# bristol_longshot.net
KiCad netlist of a schematic drawn in EAGLE
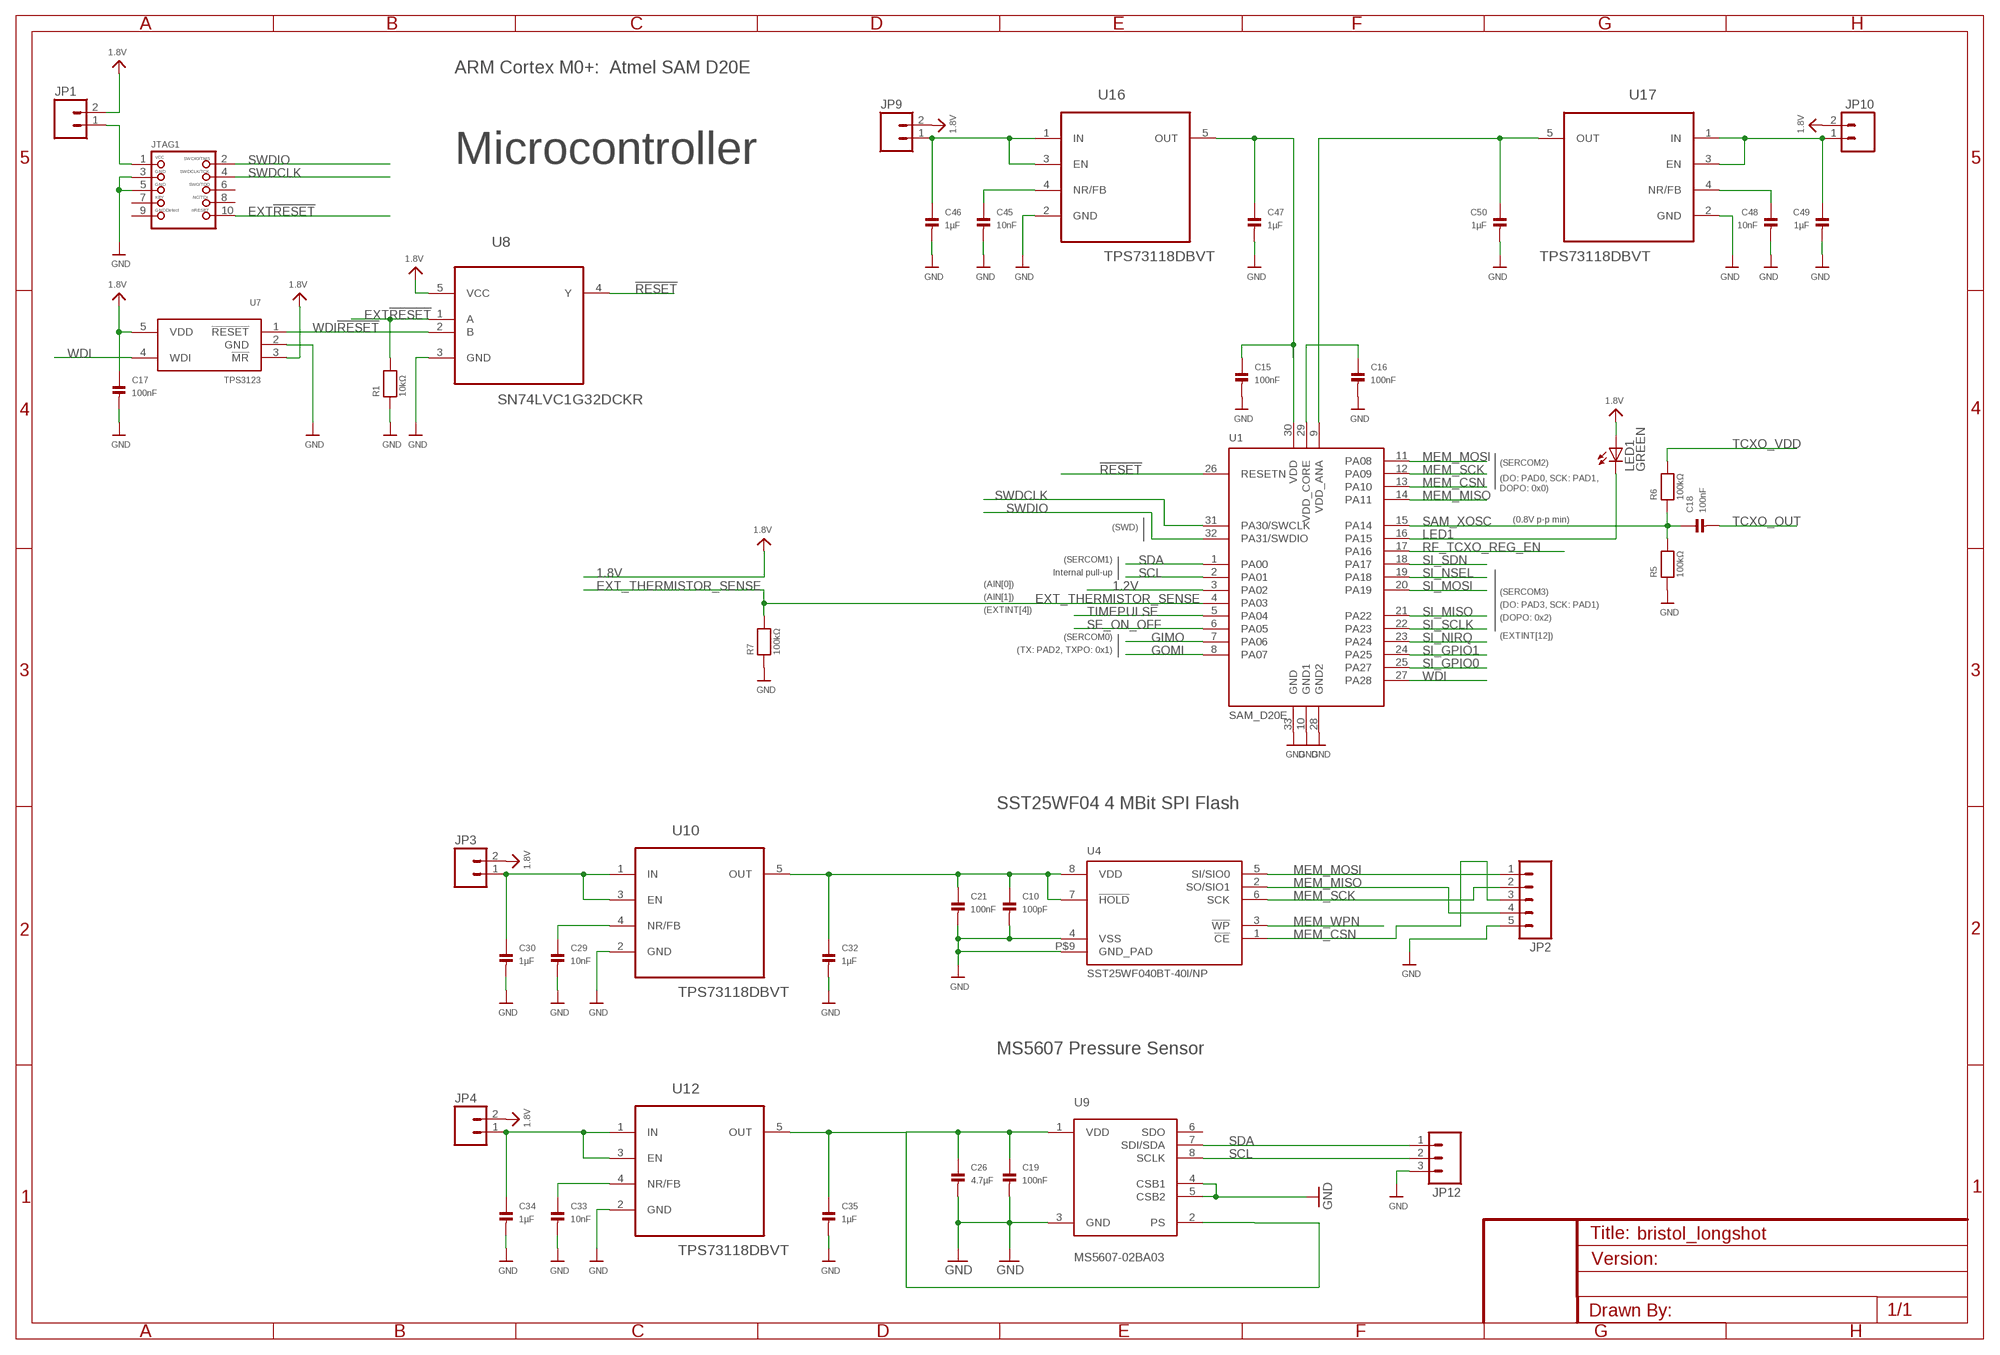
[diagram p0: schematic, sheet 1, part 1 of 2]
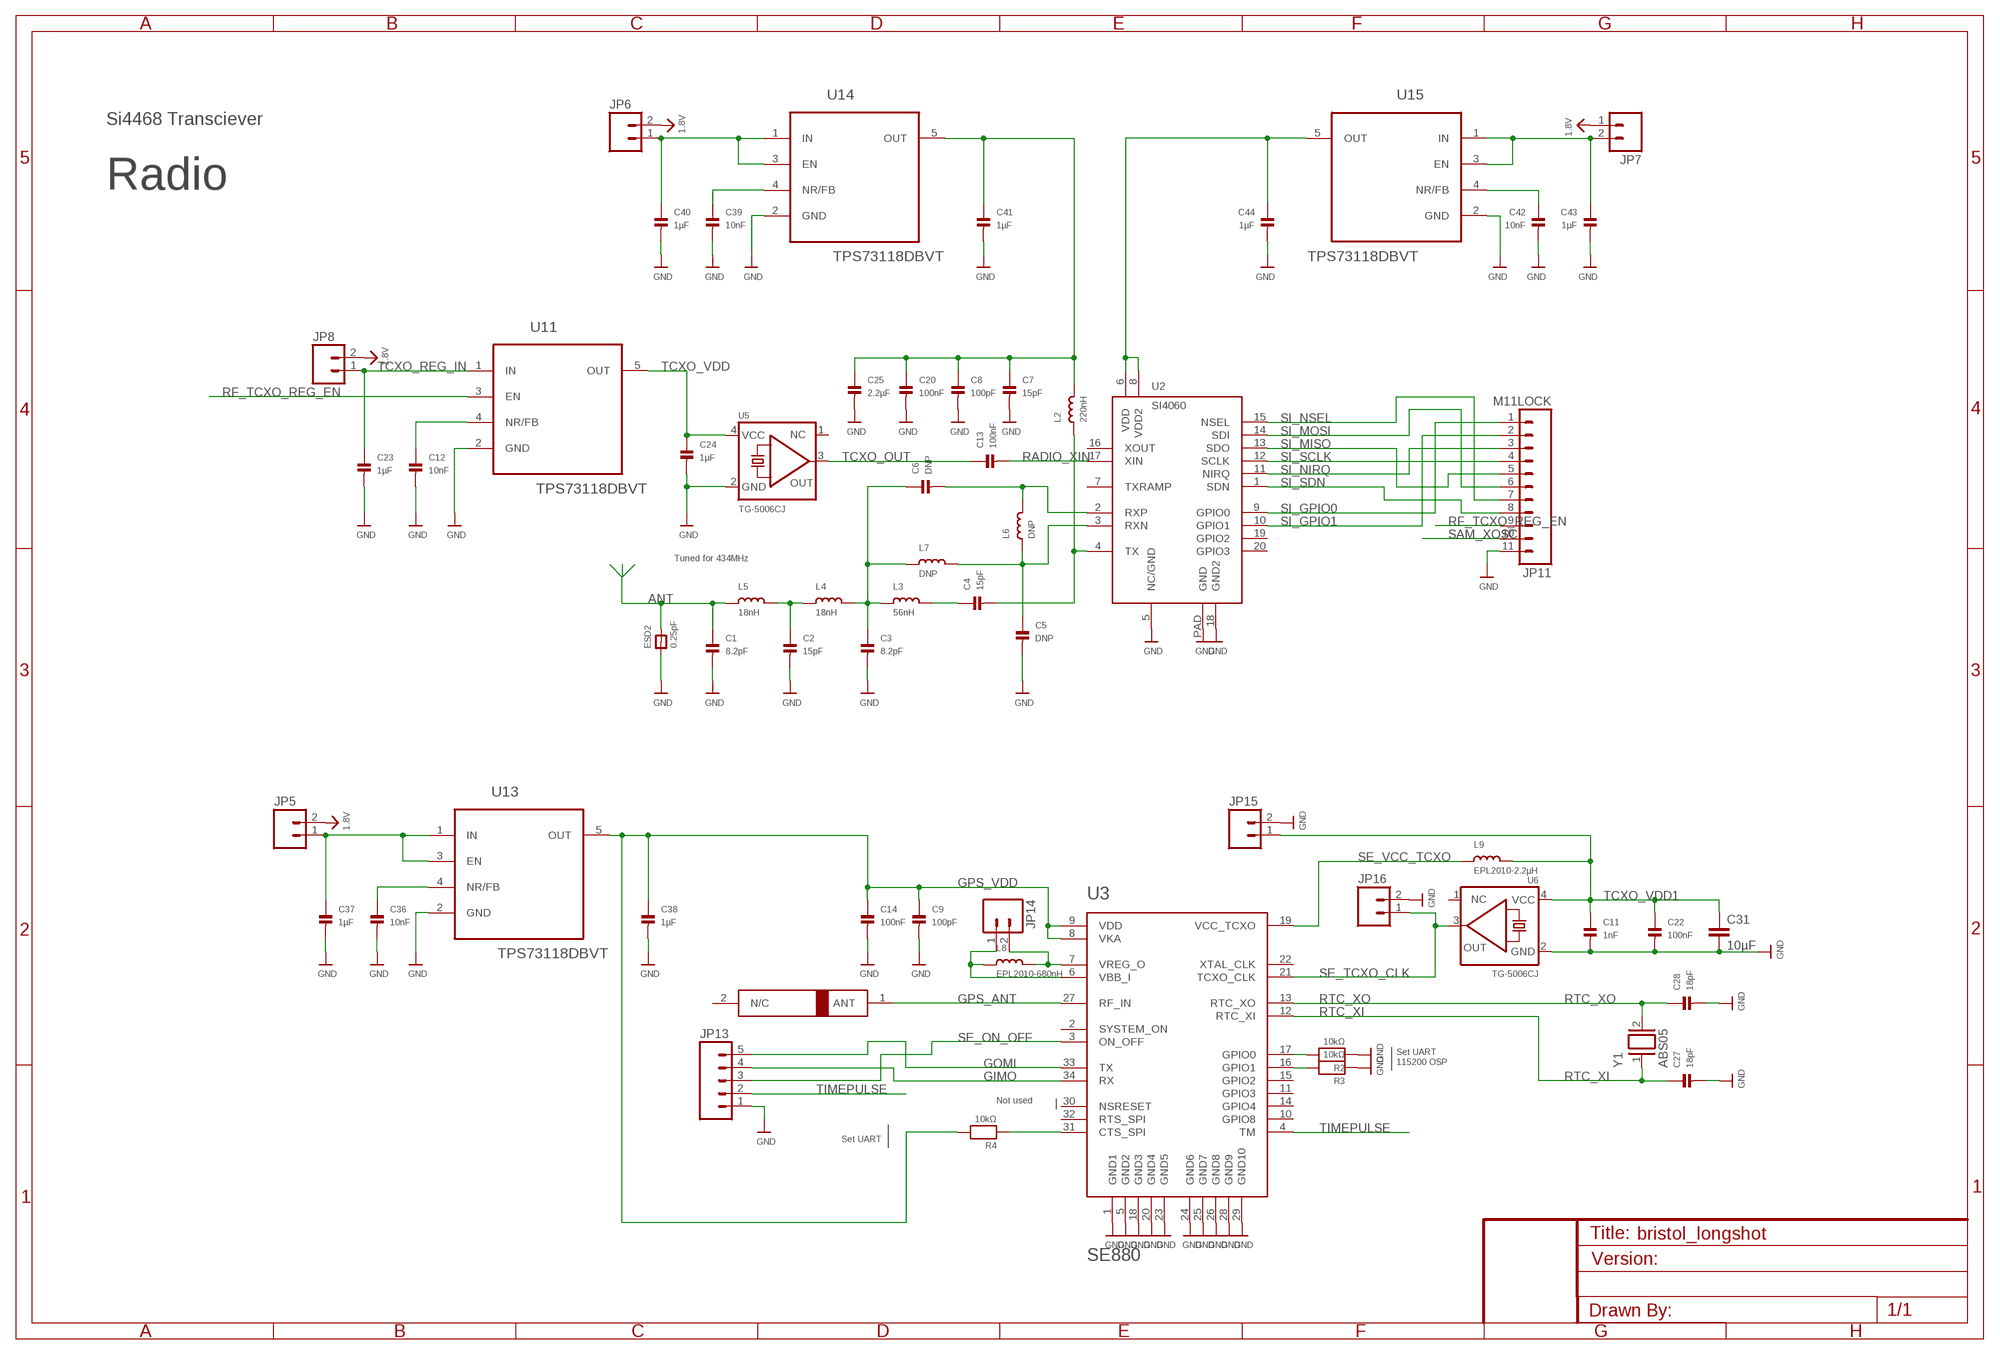
[diagram p1: schematic, sheet 1, part 2 of 2]

(export (version "E")
  (design (tool "Eeschema 10.0.6"))
  (components
    (comp (ref "A1")
      (value "1575AT43A40")
      (footprint "eagle-import:1575AT43A40")
      (libsource (lib "eagle-import") (part "1575AT43A40"))
    )
    (comp (ref "C1")
      (value "8.2pF")
      (footprint "eagle-import:_0402@2")
      (libsource (lib "eagle-import") (part "CAP_CERAMIC_0402"))
    )
    (comp (ref "C2")
      (value "15pF")
      (footprint "eagle-import:_0402@2")
      (libsource (lib "eagle-import") (part "CAP_CERAMIC_0402"))
    )
    (comp (ref "C3")
      (value "8.2pF")
      (footprint "eagle-import:_0402@2")
      (libsource (lib "eagle-import") (part "CAP_CERAMIC_0402"))
    )
    (comp (ref "C4")
      (value "15pF")
      (footprint "eagle-import:_0402@2")
      (libsource (lib "eagle-import") (part "CAP_CERAMIC_0402"))
    )
    (comp (ref "C5")
      (value "DNP")
      (footprint "eagle-import:_0402@2")
      (libsource (lib "eagle-import") (part "CAP_CERAMIC_0402"))
    )
    (comp (ref "C6")
      (value "DNP")
      (footprint "eagle-import:_0402@2")
      (libsource (lib "eagle-import") (part "CAP_CERAMIC_0402"))
    )
    (comp (ref "C7")
      (value "15pF")
      (footprint "eagle-import:_0402@2")
      (libsource (lib "eagle-import") (part "CAP_CERAMIC_0402"))
    )
    (comp (ref "C8")
      (value "100pF")
      (footprint "eagle-import:_0402@2")
      (libsource (lib "eagle-import") (part "CAP_CERAMIC_0402"))
    )
    (comp (ref "C9")
      (value "100pF")
      (footprint "eagle-import:_0402@2")
      (libsource (lib "eagle-import") (part "CAP_CERAMIC_0402"))
    )
    (comp (ref "C10")
      (value "100pF")
      (footprint "eagle-import:_0402@2")
      (libsource (lib "eagle-import") (part "CAP_CERAMIC_0402"))
    )
    (comp (ref "C11")
      (value "1nF")
      (footprint "eagle-import:_0402@2")
      (libsource (lib "eagle-import") (part "CAP_CERAMIC_0402"))
    )
    (comp (ref "C12")
      (value "10nF")
      (footprint "eagle-import:_0402@2")
      (libsource (lib "eagle-import") (part "CAP_CERAMIC_0402"))
    )
    (comp (ref "C13")
      (value "100nF")
      (footprint "eagle-import:_0402@2")
      (libsource (lib "eagle-import") (part "CAP_CERAMIC_0402"))
    )
    (comp (ref "C14")
      (value "100nF")
      (footprint "eagle-import:_0402@2")
      (libsource (lib "eagle-import") (part "CAP_CERAMIC_0402"))
    )
    (comp (ref "C15")
      (value "100nF")
      (footprint "eagle-import:_0402@2")
      (libsource (lib "eagle-import") (part "CAP_CERAMIC_0402"))
    )
    (comp (ref "C16")
      (value "100nF")
      (footprint "eagle-import:_0402@2")
      (libsource (lib "eagle-import") (part "CAP_CERAMIC_0402"))
    )
    (comp (ref "C17")
      (value "100nF")
      (footprint "eagle-import:_0402@2")
      (libsource (lib "eagle-import") (part "CAP_CERAMIC_0402"))
    )
    (comp (ref "C18")
      (value "100nF")
      (footprint "eagle-import:_0402@2")
      (libsource (lib "eagle-import") (part "CAP_CERAMIC_0402"))
    )
    (comp (ref "C19")
      (value "100nF")
      (footprint "eagle-import:_0402@2")
      (libsource (lib "eagle-import") (part "CAP_CERAMIC_0402"))
    )
    (comp (ref "C20")
      (value "100nF")
      (footprint "eagle-import:_0402@2")
      (libsource (lib "eagle-import") (part "CAP_CERAMIC_0402"))
    )
    (comp (ref "C21")
      (value "100nF")
      (footprint "eagle-import:_0402@2")
      (libsource (lib "eagle-import") (part "CAP_CERAMIC_0402"))
    )
    (comp (ref "C22")
      (value "100nF")
      (footprint "eagle-import:_0402@2")
      (libsource (lib "eagle-import") (part "CAP_CERAMIC_0402"))
    )
    (comp (ref "C23")
      (value "1µF")
      (footprint "eagle-import:_0402@2")
      (libsource (lib "eagle-import") (part "CAP_CERAMIC_0402"))
    )
    (comp (ref "C24")
      (value "1µF")
      (footprint "eagle-import:_0402@2")
      (libsource (lib "eagle-import") (part "CAP_CERAMIC_0402"))
    )
    (comp (ref "C25")
      (value "2.2µF")
      (footprint "eagle-import:_0402@2")
      (libsource (lib "eagle-import") (part "CAP_CERAMIC_0402"))
    )
    (comp (ref "C26")
      (value "4.7µF")
      (footprint "eagle-import:_0402@2")
      (libsource (lib "eagle-import") (part "CAP_CERAMIC_0402"))
    )
    (comp (ref "C27")
      (value "18pF")
      (footprint "eagle-import:_0402@2")
      (libsource (lib "eagle-import") (part "CAP_CERAMIC_0402"))
    )
    (comp (ref "C28")
      (value "18pF")
      (footprint "eagle-import:_0402@2")
      (libsource (lib "eagle-import") (part "CAP_CERAMIC_0402"))
    )
    (comp (ref "C29")
      (value "10nF")
      (footprint "eagle-import:_0402@2")
      (libsource (lib "eagle-import") (part "CAP_CERAMIC_0402"))
    )
    (comp (ref "C30")
      (value "1µF")
      (footprint "eagle-import:_0402@2")
      (libsource (lib "eagle-import") (part "CAP_CERAMIC_0402"))
    )
    (comp (ref "C31")
      (value "10µF")
      (footprint "eagle-import:C0603K")
      (libsource (lib "eagle-import") (part "C-EUC0603K"))
    )
    (comp (ref "C32")
      (value "1µF")
      (footprint "eagle-import:_0402@2")
      (libsource (lib "eagle-import") (part "CAP_CERAMIC_0402"))
    )
    (comp (ref "C33")
      (value "10nF")
      (footprint "eagle-import:_0402@2")
      (libsource (lib "eagle-import") (part "CAP_CERAMIC_0402"))
    )
    (comp (ref "C34")
      (value "1µF")
      (footprint "eagle-import:_0402@2")
      (libsource (lib "eagle-import") (part "CAP_CERAMIC_0402"))
    )
    (comp (ref "C35")
      (value "1µF")
      (footprint "eagle-import:_0402@2")
      (libsource (lib "eagle-import") (part "CAP_CERAMIC_0402"))
    )
    (comp (ref "C36")
      (value "10nF")
      (footprint "eagle-import:_0402@2")
      (libsource (lib "eagle-import") (part "CAP_CERAMIC_0402"))
    )
    (comp (ref "C37")
      (value "1µF")
      (footprint "eagle-import:_0402@2")
      (libsource (lib "eagle-import") (part "CAP_CERAMIC_0402"))
    )
    (comp (ref "C38")
      (value "1µF")
      (footprint "eagle-import:_0402@2")
      (libsource (lib "eagle-import") (part "CAP_CERAMIC_0402"))
    )
    (comp (ref "C39")
      (value "10nF")
      (footprint "eagle-import:_0402@2")
      (libsource (lib "eagle-import") (part "CAP_CERAMIC_0402"))
    )
    (comp (ref "C40")
      (value "1µF")
      (footprint "eagle-import:_0402@2")
      (libsource (lib "eagle-import") (part "CAP_CERAMIC_0402"))
    )
    (comp (ref "C41")
      (value "1µF")
      (footprint "eagle-import:_0402@2")
      (libsource (lib "eagle-import") (part "CAP_CERAMIC_0402"))
    )
    (comp (ref "C42")
      (value "10nF")
      (footprint "eagle-import:_0402@2")
      (libsource (lib "eagle-import") (part "CAP_CERAMIC_0402"))
    )
    (comp (ref "C43")
      (value "1µF")
      (footprint "eagle-import:_0402@2")
      (libsource (lib "eagle-import") (part "CAP_CERAMIC_0402"))
    )
    (comp (ref "C44")
      (value "1µF")
      (footprint "eagle-import:_0402@2")
      (libsource (lib "eagle-import") (part "CAP_CERAMIC_0402"))
    )
    (comp (ref "C45")
      (value "10nF")
      (footprint "eagle-import:_0402@2")
      (libsource (lib "eagle-import") (part "CAP_CERAMIC_0402"))
    )
    (comp (ref "C46")
      (value "1µF")
      (footprint "eagle-import:_0402@2")
      (libsource (lib "eagle-import") (part "CAP_CERAMIC_0402"))
    )
    (comp (ref "C47")
      (value "1µF")
      (footprint "eagle-import:_0402@2")
      (libsource (lib "eagle-import") (part "CAP_CERAMIC_0402"))
    )
    (comp (ref "C48")
      (value "10nF")
      (footprint "eagle-import:_0402@2")
      (libsource (lib "eagle-import") (part "CAP_CERAMIC_0402"))
    )
    (comp (ref "C49")
      (value "1µF")
      (footprint "eagle-import:_0402@2")
      (libsource (lib "eagle-import") (part "CAP_CERAMIC_0402"))
    )
    (comp (ref "C50")
      (value "1µF")
      (footprint "eagle-import:_0402@2")
      (libsource (lib "eagle-import") (part "CAP_CERAMIC_0402"))
    )
    (comp (ref "ESD2")
      (value "0.25pF")
      (footprint "eagle-import:_0603MP")
      (libsource (lib "eagle-import") (part "FERRITE_0603MP"))
    )
    (comp (ref "JP1")
      (value "M02LOCK")
      (footprint "eagle-import:1X02_LOCK")
      (libsource (lib "eagle-import") (part "M02LOCK"))
    )
    (comp (ref "JP2")
      (value "M05LOCK")
      (footprint "eagle-import:1X05_LOCK")
      (libsource (lib "eagle-import") (part "M05LOCK"))
    )
    (comp (ref "JP3")
      (value "M02LOCK")
      (footprint "eagle-import:1X02_LOCK")
      (libsource (lib "eagle-import") (part "M02LOCK"))
    )
    (comp (ref "JP4")
      (value "M02LOCK")
      (footprint "eagle-import:1X02_LOCK")
      (libsource (lib "eagle-import") (part "M02LOCK"))
    )
    (comp (ref "JP5")
      (value "M02LOCK")
      (footprint "eagle-import:1X02_LOCK")
      (libsource (lib "eagle-import") (part "M02LOCK"))
    )
    (comp (ref "JP6")
      (value "M02LOCK")
      (footprint "eagle-import:1X02_LOCK")
      (libsource (lib "eagle-import") (part "M02LOCK"))
    )
    (comp (ref "JP7")
      (value "M02LOCK")
      (footprint "eagle-import:1X02_LOCK")
      (libsource (lib "eagle-import") (part "M02LOCK"))
    )
    (comp (ref "JP8")
      (value "M02LOCK")
      (footprint "eagle-import:1X02_LOCK")
      (libsource (lib "eagle-import") (part "M02LOCK"))
    )
    (comp (ref "JP9")
      (value "M02LOCK")
      (footprint "eagle-import:1X02_LOCK")
      (libsource (lib "eagle-import") (part "M02LOCK"))
    )
    (comp (ref "JP10")
      (value "M02LOCK")
      (footprint "eagle-import:1X02_LOCK")
      (libsource (lib "eagle-import") (part "M02LOCK"))
    )
    (comp (ref "JP11")
      (value "M11LOCK")
      (footprint "eagle-import:1X11_LOCK")
      (libsource (lib "eagle-import") (part "M11LOCK"))
    )
    (comp (ref "JP12")
      (value "M03LOCK")
      (footprint "eagle-import:1X03_LOCK")
      (libsource (lib "eagle-import") (part "M03LOCK"))
    )
    (comp (ref "JP13")
      (value "M05LOCK")
      (footprint "eagle-import:1X05_LOCK")
      (libsource (lib "eagle-import") (part "M05LOCK"))
    )
    (comp (ref "JP14")
      (value "M02LOCK")
      (footprint "eagle-import:1X02_LOCK")
      (libsource (lib "eagle-import") (part "M02LOCK"))
    )
    (comp (ref "JP15")
      (value "M02LOCK")
      (footprint "eagle-import:1X02_LOCK")
      (libsource (lib "eagle-import") (part "M02LOCK"))
    )
    (comp (ref "JP16")
      (value "M02LOCK")
      (footprint "eagle-import:1X02_LOCK")
      (libsource (lib "eagle-import") (part "M02LOCK"))
    )
    (comp (ref "JTAG1")
      (value "JTAG-CORTEXM3SMT")
      (footprint "eagle-import:2X05_1.27MM_SMT")
      (libsource (lib "eagle-import") (part "JTAG-CORTEXM3SMT"))
    )
    (comp (ref "L2")
      (value "220nH")
      (footprint "eagle-import:_0402@1")
      (libsource (lib "eagle-import") (part "INDUCTOR_0402"))
    )
    (comp (ref "L3")
      (value "56nH")
      (footprint "eagle-import:_0402@1")
      (libsource (lib "eagle-import") (part "INDUCTOR_0402"))
    )
    (comp (ref "L4")
      (value "18nH")
      (footprint "eagle-import:_0402@1")
      (libsource (lib "eagle-import") (part "INDUCTOR_0402"))
    )
    (comp (ref "L5")
      (value "18nH")
      (footprint "eagle-import:_0402@1")
      (libsource (lib "eagle-import") (part "INDUCTOR_0402"))
    )
    (comp (ref "L6")
      (value "DNP")
      (footprint "eagle-import:_0402@1")
      (libsource (lib "eagle-import") (part "INDUCTOR_0402"))
    )
    (comp (ref "L7")
      (value "DNP")
      (footprint "eagle-import:_0402@1")
      (libsource (lib "eagle-import") (part "INDUCTOR_0402"))
    )
    (comp (ref "L8")
      (value "EPL2010-680nH")
      (footprint "eagle-import:EPL2010")
      (libsource (lib "eagle-import") (part "EPL2010"))
    )
    (comp (ref "L9")
      (value "EPL2010-2.2µH")
      (footprint "eagle-import:EPL2010")
      (libsource (lib "eagle-import") (part "EPL2010"))
    )
    (comp (ref "LED1")
      (value "GREEN")
      (footprint "eagle-import:CHIPLED_0603")
      (libsource (lib "eagle-import") (part "LEDCHIPLED_0603"))
    )
    (comp (ref "R1")
      (value "10kΩ")
      (footprint "eagle-import:_0402")
      (libsource (lib "eagle-import") (part "RESISTOR_0402"))
    )
    (comp (ref "R2")
      (value "10kΩ")
      (footprint "eagle-import:_0402")
      (libsource (lib "eagle-import") (part "RESISTOR_0402"))
    )
    (comp (ref "R3")
      (value "10kΩ")
      (footprint "eagle-import:_0402")
      (libsource (lib "eagle-import") (part "RESISTOR_0402"))
    )
    (comp (ref "R4")
      (value "10kΩ")
      (footprint "eagle-import:_0402")
      (libsource (lib "eagle-import") (part "RESISTOR_0402"))
    )
    (comp (ref "R5")
      (value "100kΩ")
      (footprint "eagle-import:_0402")
      (libsource (lib "eagle-import") (part "RESISTOR_0402"))
    )
    (comp (ref "R6")
      (value "100kΩ")
      (footprint "eagle-import:_0402")
      (libsource (lib "eagle-import") (part "RESISTOR_0402"))
    )
    (comp (ref "R7")
      (value "100kΩ")
      (footprint "eagle-import:_0402")
      (libsource (lib "eagle-import") (part "RESISTOR_0402"))
    )
    (comp (ref "U1")
      (value "SAM_D20E")
      (footprint "eagle-import:QFN32_5MM")
      (libsource (lib "eagle-import") (part "SAM_D20E"))
    )
    (comp (ref "U2")
      (value "SI4060")
      (footprint "eagle-import:QFN20")
      (libsource (lib "eagle-import") (part "SI4060"))
    )
    (comp (ref "U3")
      (value "SE880")
      (footprint "eagle-import:SE880")
      (libsource (lib "eagle-import") (part "SE880"))
    )
    (comp (ref "U4")
      (value "SST25WF040BT-40I/NP")
      (footprint "eagle-import:USON-8")
      (libsource (lib "eagle-import") (part "SST25WF040BT-40I/NP"))
    )
    (comp (ref "U5")
      (value "TG-5006CJ")
      (footprint "eagle-import:TC-5006CJ")
      (libsource (lib "eagle-import") (part "TG-5006CJ"))
    )
    (comp (ref "U6")
      (value "TG-5006CJ")
      (footprint "eagle-import:TC-5006CJ")
      (libsource (lib "eagle-import") (part "TG-5006CJ"))
    )
    (comp (ref "U7")
      (value "TPS3123")
      (footprint "eagle-import:SOT23-5")
      (libsource (lib "eagle-import") (part "TPS3123"))
    )
    (comp (ref "U8")
      (value "SN74LVC1G32DCKR")
      (footprint "eagle-import:SOT65P210X110-5N")
      (libsource (lib "eagle-import") (part "SN74LVC1G32DCKR"))
    )
    (comp (ref "U9")
      (value "MS5607-02BA03")
      (footprint "eagle-import:MS5607-02BA03")
      (libsource (lib "eagle-import") (part "MS5607-02BA03"))
    )
    (comp (ref "U10")
      (value "TPS73118DBVT")
      (footprint "eagle-import:SOT95P280X145-5N")
      (libsource (lib "eagle-import") (part "TPS73118DBVT"))
    )
    (comp (ref "U11")
      (value "TPS73118DBVT")
      (footprint "eagle-import:SOT95P280X145-5N")
      (libsource (lib "eagle-import") (part "TPS73118DBVT"))
    )
    (comp (ref "U12")
      (value "TPS73118DBVT")
      (footprint "eagle-import:SOT95P280X145-5N")
      (libsource (lib "eagle-import") (part "TPS73118DBVT"))
    )
    (comp (ref "U13")
      (value "TPS73118DBVT")
      (footprint "eagle-import:SOT95P280X145-5N")
      (libsource (lib "eagle-import") (part "TPS73118DBVT"))
    )
    (comp (ref "U14")
      (value "TPS73118DBVT")
      (footprint "eagle-import:SOT95P280X145-5N")
      (libsource (lib "eagle-import") (part "TPS73118DBVT"))
    )
    (comp (ref "U15")
      (value "TPS73118DBVT")
      (footprint "eagle-import:SOT95P280X145-5N")
      (libsource (lib "eagle-import") (part "TPS73118DBVT"))
    )
    (comp (ref "U16")
      (value "TPS73118DBVT")
      (footprint "eagle-import:SOT95P280X145-5N")
      (libsource (lib "eagle-import") (part "TPS73118DBVT"))
    )
    (comp (ref "U17")
      (value "TPS73118DBVT")
      (footprint "eagle-import:SOT95P280X145-5N")
      (libsource (lib "eagle-import") (part "TPS73118DBVT"))
    )
    (comp (ref "Y1")
      (value "ABS05")
      (footprint "eagle-import:ABS05")
      (libsource (lib "eagle-import") (part "ABS05"))
    )
  )
  (nets
    (net (code "1") (name "/1.2V") (class "Default")
      (node (ref "U1") (pin "3") (pinfunction "PA02_3") (pintype "bidirectional"))
    )
    (net (code "2") (name "/ANT") (class "Default")
      (node (ref "C1") (pin "1") (pinfunction "P$1_1") (pintype "passive"))
      (node (ref "ESD2") (pin "2") (pinfunction "P$2_2") (pintype "passive"))
      (node (ref "L5") (pin "1") (pinfunction "1_1") (pintype "passive"))
    )
    (net (code "3") (name "/EXT_THERMISTOR_SENSE") (class "Default")
      (node (ref "R7") (pin "2") (pinfunction "2_2") (pintype "passive"))
      (node (ref "U1") (pin "4") (pinfunction "PA03_4") (pintype "bidirectional"))
    )
    (net (code "4") (name "/EXT~{RESET}") (class "Default")
      (node (ref "JTAG1") (pin "10") (pinfunction "10_10") (pintype "passive"))
      (node (ref "R1") (pin "2") (pinfunction "2_2") (pintype "passive"))
      (node (ref "U8") (pin "1") (pinfunction "A_1") (pintype "input"))
    )
    (net (code "5") (name "/GIMO") (class "Default")
      (node (ref "JP13") (pin "4") (pinfunction "4_4") (pintype "passive"))
      (node (ref "U1") (pin "7") (pinfunction "PA06_7") (pintype "bidirectional"))
      (node (ref "U3") (pin "34") (pinfunction "RX_34") (pintype "bidirectional"))
    )
    (net (code "6") (name "/GOMI") (class "Default")
      (node (ref "JP13") (pin "5") (pinfunction "5_5") (pintype "passive"))
      (node (ref "U1") (pin "8") (pinfunction "PA07_8") (pintype "bidirectional"))
      (node (ref "U3") (pin "33") (pinfunction "TX_33") (pintype "bidirectional"))
    )
    (net (code "7") (name "/GPS_ANT") (class "Default")
      (node (ref "A1") (pin "1") (pinfunction "ANT_1") (pintype "bidirectional"))
      (node (ref "U3") (pin "27") (pinfunction "RF_IN_27") (pintype "bidirectional"))
    )
    (net (code "8") (name "/GPS_VDD") (class "Default")
      (node (ref "C14") (pin "1") (pinfunction "P$1_1") (pintype "passive"))
      (node (ref "C38") (pin "1") (pinfunction "P$1_1") (pintype "passive"))
      (node (ref "C9") (pin "1") (pinfunction "P$1_1") (pintype "passive"))
      (node (ref "R4") (pin "2") (pinfunction "2_2") (pintype "passive"))
      (node (ref "U13") (pin "5") (pinfunction "OUT_5") (pintype "output"))
      (node (ref "U3") (pin "8") (pinfunction "VKA_8") (pintype "bidirectional"))
      (node (ref "U3") (pin "9") (pinfunction "VDD_9") (pintype "bidirectional"))
    )
    (net (code "9") (name "/LED1") (class "Default")
      (node (ref "LED1") (pin "C") (pinfunction "C_C") (pintype "passive"))
      (node (ref "U1") (pin "16") (pinfunction "PA15_16") (pintype "bidirectional"))
    )
    (net (code "10") (name "/MEM_CSN") (class "Default")
      (node (ref "JP2") (pin "3") (pinfunction "3_3") (pintype "passive"))
      (node (ref "U1") (pin "13") (pinfunction "PA10_13") (pintype "bidirectional"))
      (node (ref "U4") (pin "1") (pinfunction "~{CE}_1") (pintype "input"))
    )
    (net (code "11") (name "/MEM_MISO") (class "Default")
      (node (ref "JP2") (pin "4") (pinfunction "4_4") (pintype "passive"))
      (node (ref "U1") (pin "14") (pinfunction "PA11_14") (pintype "bidirectional"))
      (node (ref "U4") (pin "2") (pinfunction "SO/SIO1_2") (pintype "output"))
    )
    (net (code "12") (name "/MEM_MOSI") (class "Default")
      (node (ref "JP2") (pin "1") (pinfunction "1_1") (pintype "passive"))
      (node (ref "U1") (pin "11") (pinfunction "PA08_11") (pintype "bidirectional"))
      (node (ref "U4") (pin "5") (pinfunction "SI/SIO0_5") (pintype "bidirectional"))
    )
    (net (code "13") (name "/MEM_SCK") (class "Default")
      (node (ref "JP2") (pin "2") (pinfunction "2_2") (pintype "passive"))
      (node (ref "U1") (pin "12") (pinfunction "PA09_12") (pintype "bidirectional"))
      (node (ref "U4") (pin "6") (pinfunction "SCK_6") (pintype "input"))
    )
    (net (code "14") (name "/MEM_WPN") (class "Default")
      (node (ref "U4") (pin "3") (pinfunction "~{WP}_3") (pintype "output"))
    )
    (net (code "15") (name "/RADIO_XIN") (class "Default")
      (node (ref "C13") (pin "2") (pinfunction "P$2_2") (pintype "passive"))
      (node (ref "U2") (pin "17") (pinfunction "XIN_17") (pintype "input"))
    )
    (net (code "16") (name "/RF_TCXO_REG_EN") (class "Default")
      (node (ref "JP11") (pin "9") (pinfunction "9_9") (pintype "passive"))
      (node (ref "U1") (pin "17") (pinfunction "PA16_17") (pintype "bidirectional"))
      (node (ref "U11") (pin "3") (pinfunction "EN_3") (pintype "input"))
    )
    (net (code "17") (name "/RTC_XI") (class "Default")
      (node (ref "C27") (pin "1") (pinfunction "P$1_1") (pintype "passive"))
      (node (ref "U3") (pin "12") (pinfunction "RTC_XI_12") (pintype "bidirectional"))
      (node (ref "Y1") (pin "1") (pinfunction "1_1") (pintype "passive"))
    )
    (net (code "18") (name "/RTC_XO") (class "Default")
      (node (ref "C28") (pin "1") (pinfunction "P$1_1") (pintype "passive"))
      (node (ref "U3") (pin "13") (pinfunction "RTC_XO_13") (pintype "bidirectional"))
      (node (ref "Y1") (pin "2") (pinfunction "2_2") (pintype "passive"))
    )
    (net (code "19") (name "/SAM_XOSC") (class "Default")
      (node (ref "C18") (pin "1") (pinfunction "P$1_1") (pintype "passive"))
      (node (ref "JP11") (pin "10") (pinfunction "10_10") (pintype "passive"))
      (node (ref "R5") (pin "2") (pinfunction "2_2") (pintype "passive"))
      (node (ref "R6") (pin "1") (pinfunction "1_1") (pintype "passive"))
      (node (ref "U1") (pin "15") (pinfunction "PA14_15") (pintype "bidirectional"))
    )
    (net (code "20") (name "/SCL") (class "Default")
      (node (ref "JP12") (pin "2") (pinfunction "2_2") (pintype "passive"))
      (node (ref "U1") (pin "2") (pinfunction "PA01_2") (pintype "bidirectional"))
      (node (ref "U9") (pin "8") (pinfunction "SCLK_8") (pintype "bidirectional"))
    )
    (net (code "21") (name "/SDA") (class "Default")
      (node (ref "JP12") (pin "1") (pinfunction "1_1") (pintype "passive"))
      (node (ref "U1") (pin "1") (pinfunction "PA00_1") (pintype "bidirectional"))
      (node (ref "U9") (pin "7") (pinfunction "SDI/SDA_7") (pintype "bidirectional"))
    )
    (net (code "22") (name "/SE_ON_OFF") (class "Default")
      (node (ref "JP13") (pin "3") (pinfunction "3_3") (pintype "passive"))
      (node (ref "U1") (pin "6") (pinfunction "PA05_6") (pintype "bidirectional"))
      (node (ref "U3") (pin "3") (pinfunction "ON_OFF_3") (pintype "bidirectional"))
    )
    (net (code "23") (name "/SE_TCXO_CLK") (class "Default")
      (node (ref "JP16") (pin "1") (pinfunction "1_1") (pintype "passive"))
      (node (ref "U3") (pin "21") (pinfunction "TCXO_CLK_21") (pintype "bidirectional"))
      (node (ref "U6") (pin "3") (pinfunction "OUT_3") (pintype "output"))
    )
    (net (code "24") (name "/SE_VCC_TCXO") (class "Default")
      (node (ref "L9") (pin "1") (pinfunction "1_1") (pintype "passive"))
      (node (ref "U3") (pin "19") (pinfunction "VCC_TCXO_19") (pintype "bidirectional"))
    )
    (net (code "25") (name "/SI_GPIO0") (class "Default")
      (node (ref "JP11") (pin "1") (pinfunction "1_1") (pintype "passive"))
      (node (ref "U1") (pin "25") (pinfunction "PA27_25") (pintype "bidirectional"))
      (node (ref "U2") (pin "9") (pinfunction "GPIO0_9") (pintype "bidirectional"))
    )
    (net (code "26") (name "/SI_GPIO1") (class "Default")
      (node (ref "JP11") (pin "2") (pinfunction "2_2") (pintype "passive"))
      (node (ref "U1") (pin "24") (pinfunction "PA25_24") (pintype "bidirectional"))
      (node (ref "U2") (pin "10") (pinfunction "GPIO1_10") (pintype "bidirectional"))
    )
    (net (code "27") (name "/SI_MISO") (class "Default")
      (node (ref "JP11") (pin "5") (pinfunction "5_5") (pintype "passive"))
      (node (ref "U1") (pin "21") (pinfunction "PA22_21") (pintype "bidirectional"))
      (node (ref "U2") (pin "13") (pinfunction "SDO_13") (pintype "output"))
    )
    (net (code "28") (name "/SI_MOSI") (class "Default")
      (node (ref "JP11") (pin "6") (pinfunction "6_6") (pintype "passive"))
      (node (ref "U1") (pin "20") (pinfunction "PA19_20") (pintype "bidirectional"))
      (node (ref "U2") (pin "14") (pinfunction "SDI_14") (pintype "bidirectional"))
    )
    (net (code "29") (name "/SI_NIRQ") (class "Default")
      (node (ref "JP11") (pin "3") (pinfunction "3_3") (pintype "passive"))
      (node (ref "U1") (pin "23") (pinfunction "PA24_23") (pintype "bidirectional"))
      (node (ref "U2") (pin "11") (pinfunction "NIRQ_11") (pintype "output"))
    )
    (net (code "30") (name "/SI_NSEL") (class "Default")
      (node (ref "JP11") (pin "7") (pinfunction "7_7") (pintype "passive"))
      (node (ref "U1") (pin "19") (pinfunction "PA18_19") (pintype "bidirectional"))
      (node (ref "U2") (pin "15") (pinfunction "NSEL_15") (pintype "input"))
    )
    (net (code "31") (name "/SI_SCLK") (class "Default")
      (node (ref "JP11") (pin "4") (pinfunction "4_4") (pintype "passive"))
      (node (ref "U1") (pin "22") (pinfunction "PA23_22") (pintype "bidirectional"))
      (node (ref "U2") (pin "12") (pinfunction "SCLK_12") (pintype "input"))
    )
    (net (code "32") (name "/SI_SDN") (class "Default")
      (node (ref "JP11") (pin "8") (pinfunction "8_8") (pintype "passive"))
      (node (ref "U1") (pin "18") (pinfunction "PA17_18") (pintype "bidirectional"))
      (node (ref "U2") (pin "1") (pinfunction "SDN_1") (pintype "input"))
    )
    (net (code "33") (name "/SWDCLK") (class "Default")
      (node (ref "JTAG1") (pin "4") (pinfunction "4_4") (pintype "passive"))
      (node (ref "U1") (pin "31") (pinfunction "PA30/SWCLK_31") (pintype "bidirectional"))
    )
    (net (code "34") (name "/SWDIO") (class "Default")
      (node (ref "JTAG1") (pin "2") (pinfunction "2_2") (pintype "passive"))
      (node (ref "U1") (pin "32") (pinfunction "PA31/SWDIO_32") (pintype "bidirectional"))
    )
    (net (code "35") (name "/TCXO_OUT") (class "Default")
      (node (ref "C13") (pin "1") (pinfunction "P$1_1") (pintype "passive"))
      (node (ref "C18") (pin "2") (pinfunction "P$2_2") (pintype "passive"))
      (node (ref "U5") (pin "3") (pinfunction "OUT_3") (pintype "output"))
    )
    (net (code "36") (name "/TCXO_REG_IN") (class "Default")
      (node (ref "C23") (pin "1") (pinfunction "P$1_1") (pintype "passive"))
      (node (ref "JP8") (pin "1") (pinfunction "1_1") (pintype "passive"))
      (node (ref "U11") (pin "1") (pinfunction "IN_1") (pintype "power_in"))
    )
    (net (code "37") (name "/TCXO_VDD") (class "Default")
      (node (ref "C24") (pin "1") (pinfunction "P$1_1") (pintype "passive"))
      (node (ref "R6") (pin "2") (pinfunction "2_2") (pintype "passive"))
      (node (ref "U11") (pin "5") (pinfunction "OUT_5") (pintype "output"))
      (node (ref "U5") (pin "4") (pinfunction "VCC_4") (pintype "power_in"))
    )
    (net (code "38") (name "/TCXO_VDD1") (class "Default")
      (node (ref "C11") (pin "1") (pinfunction "P$1_1") (pintype "passive"))
      (node (ref "C22") (pin "1") (pinfunction "P$1_1") (pintype "passive"))
      (node (ref "C31") (pin "1") (pinfunction "1_1") (pintype "passive"))
      (node (ref "JP15") (pin "1") (pinfunction "1_1") (pintype "passive"))
      (node (ref "L9") (pin "2") (pinfunction "2_2") (pintype "passive"))
      (node (ref "U6") (pin "4") (pinfunction "VCC_4") (pintype "power_in"))
    )
    (net (code "39") (name "/TIMEPULSE") (class "Default")
      (node (ref "JP13") (pin "2") (pinfunction "2_2") (pintype "passive"))
      (node (ref "U1") (pin "5") (pinfunction "PA04_5") (pintype "bidirectional"))
      (node (ref "U3") (pin "4") (pinfunction "TM_4") (pintype "bidirectional"))
    )
    (net (code "40") (name "/WDI") (class "Default")
      (node (ref "U1") (pin "27") (pinfunction "PA28_27") (pintype "bidirectional"))
      (node (ref "U7") (pin "4") (pinfunction "WDI_4") (pintype "bidirectional"))
    )
    (net (code "41") (name "/WDI~{RESET}") (class "Default")
      (node (ref "U7") (pin "1") (pinfunction "~{RESET}_1") (pintype "bidirectional"))
      (node (ref "U8") (pin "2") (pinfunction "B_2") (pintype "input"))
    )
    (net (code "42") (name "/~{RESET}") (class "Default")
      (node (ref "U1") (pin "26") (pinfunction "RESETN_26") (pintype "input"))
      (node (ref "U8") (pin "4") (pinfunction "Y_4") (pintype "output"))
    )
    (net (code "43") (name "1.8V") (class "Default")
      (node (ref "C17") (pin "1") (pinfunction "P$1_1") (pintype "passive"))
      (node (ref "JP1") (pin "2") (pinfunction "2_2") (pintype "passive"))
      (node (ref "JP10") (pin "2") (pinfunction "2_2") (pintype "passive"))
      (node (ref "JP3") (pin "2") (pinfunction "2_2") (pintype "passive"))
      (node (ref "JP4") (pin "2") (pinfunction "2_2") (pintype "passive"))
      (node (ref "JP5") (pin "2") (pinfunction "2_2") (pintype "passive"))
      (node (ref "JP6") (pin "2") (pinfunction "2_2") (pintype "passive"))
      (node (ref "JP7") (pin "1") (pinfunction "1_1") (pintype "passive"))
      (node (ref "JP8") (pin "2") (pinfunction "2_2") (pintype "passive"))
      (node (ref "JP9") (pin "2") (pinfunction "2_2") (pintype "passive"))
      (node (ref "LED1") (pin "A") (pinfunction "A_A") (pintype "passive"))
      (node (ref "U7") (pin "3") (pinfunction "~{MR}_3") (pintype "bidirectional"))
      (node (ref "U7") (pin "5") (pinfunction "VDD_5") (pintype "bidirectional"))
      (node (ref "U8") (pin "5") (pinfunction "VCC_5") (pintype "power_in"))
    )
    (net (code "44") (name "GND") (class "Default")
      (node (ref "C1") (pin "2") (pinfunction "P$2_2") (pintype "passive"))
      (node (ref "C10") (pin "2") (pinfunction "P$2_2") (pintype "passive"))
      (node (ref "C11") (pin "2") (pinfunction "P$2_2") (pintype "passive"))
      (node (ref "C12") (pin "2") (pinfunction "P$2_2") (pintype "passive"))
      (node (ref "C14") (pin "2") (pinfunction "P$2_2") (pintype "passive"))
      (node (ref "C15") (pin "2") (pinfunction "P$2_2") (pintype "passive"))
      (node (ref "C16") (pin "2") (pinfunction "P$2_2") (pintype "passive"))
      (node (ref "C17") (pin "2") (pinfunction "P$2_2") (pintype "passive"))
      (node (ref "C19") (pin "2") (pinfunction "P$2_2") (pintype "passive"))
      (node (ref "C2") (pin "2") (pinfunction "P$2_2") (pintype "passive"))
      (node (ref "C20") (pin "2") (pinfunction "P$2_2") (pintype "passive"))
      (node (ref "C21") (pin "2") (pinfunction "P$2_2") (pintype "passive"))
      (node (ref "C22") (pin "2") (pinfunction "P$2_2") (pintype "passive"))
      (node (ref "C23") (pin "2") (pinfunction "P$2_2") (pintype "passive"))
      (node (ref "C24") (pin "2") (pinfunction "P$2_2") (pintype "passive"))
      (node (ref "C25") (pin "2") (pinfunction "P$2_2") (pintype "passive"))
      (node (ref "C26") (pin "2") (pinfunction "P$2_2") (pintype "passive"))
      (node (ref "C27") (pin "2") (pinfunction "P$2_2") (pintype "passive"))
      (node (ref "C28") (pin "2") (pinfunction "P$2_2") (pintype "passive"))
      (node (ref "C29") (pin "2") (pinfunction "P$2_2") (pintype "passive"))
      (node (ref "C3") (pin "2") (pinfunction "P$2_2") (pintype "passive"))
      (node (ref "C30") (pin "2") (pinfunction "P$2_2") (pintype "passive"))
      (node (ref "C31") (pin "2") (pinfunction "2_2") (pintype "passive"))
      (node (ref "C32") (pin "2") (pinfunction "P$2_2") (pintype "passive"))
      (node (ref "C33") (pin "2") (pinfunction "P$2_2") (pintype "passive"))
      (node (ref "C34") (pin "2") (pinfunction "P$2_2") (pintype "passive"))
      (node (ref "C35") (pin "2") (pinfunction "P$2_2") (pintype "passive"))
      (node (ref "C36") (pin "2") (pinfunction "P$2_2") (pintype "passive"))
      (node (ref "C37") (pin "2") (pinfunction "P$2_2") (pintype "passive"))
      (node (ref "C38") (pin "2") (pinfunction "P$2_2") (pintype "passive"))
      (node (ref "C39") (pin "2") (pinfunction "P$2_2") (pintype "passive"))
      (node (ref "C40") (pin "2") (pinfunction "P$2_2") (pintype "passive"))
      (node (ref "C41") (pin "2") (pinfunction "P$2_2") (pintype "passive"))
      (node (ref "C42") (pin "2") (pinfunction "P$2_2") (pintype "passive"))
      (node (ref "C43") (pin "2") (pinfunction "P$2_2") (pintype "passive"))
      (node (ref "C44") (pin "2") (pinfunction "P$2_2") (pintype "passive"))
      (node (ref "C45") (pin "2") (pinfunction "P$2_2") (pintype "passive"))
      (node (ref "C46") (pin "2") (pinfunction "P$2_2") (pintype "passive"))
      (node (ref "C47") (pin "2") (pinfunction "P$2_2") (pintype "passive"))
      (node (ref "C48") (pin "2") (pinfunction "P$2_2") (pintype "passive"))
      (node (ref "C49") (pin "2") (pinfunction "P$2_2") (pintype "passive"))
      (node (ref "C5") (pin "2") (pinfunction "P$2_2") (pintype "passive"))
      (node (ref "C50") (pin "2") (pinfunction "P$2_2") (pintype "passive"))
      (node (ref "C7") (pin "2") (pinfunction "P$2_2") (pintype "passive"))
      (node (ref "C8") (pin "2") (pinfunction "P$2_2") (pintype "passive"))
      (node (ref "C9") (pin "2") (pinfunction "P$2_2") (pintype "passive"))
      (node (ref "ESD2") (pin "1") (pinfunction "P$1_1") (pintype "passive"))
      (node (ref "JP11") (pin "11") (pinfunction "11_11") (pintype "passive"))
      (node (ref "JP12") (pin "3") (pinfunction "3_3") (pintype "passive"))
      (node (ref "JP13") (pin "1") (pinfunction "1_1") (pintype "passive"))
      (node (ref "JP15") (pin "2") (pinfunction "2_2") (pintype "passive"))
      (node (ref "JP16") (pin "2") (pinfunction "2_2") (pintype "passive"))
      (node (ref "JP2") (pin "5") (pinfunction "5_5") (pintype "passive"))
      (node (ref "JTAG1") (pin "3") (pinfunction "3_3") (pintype "passive"))
      (node (ref "JTAG1") (pin "5") (pinfunction "5_5") (pintype "passive"))
      (node (ref "R1") (pin "1") (pinfunction "1_1") (pintype "passive"))
      (node (ref "R2") (pin "1") (pinfunction "1_1") (pintype "passive"))
      (node (ref "R3") (pin "1") (pinfunction "1_1") (pintype "passive"))
      (node (ref "R5") (pin "1") (pinfunction "1_1") (pintype "passive"))
      (node (ref "R7") (pin "1") (pinfunction "1_1") (pintype "passive"))
      (node (ref "U1") (pin "10") (pinfunction "GND1_10") (pintype "power_in"))
      (node (ref "U1") (pin "28") (pinfunction "GND2_28") (pintype "power_in"))
      (node (ref "U1") (pin "33") (pinfunction "GND_33") (pintype "power_in"))
      (node (ref "U10") (pin "2") (pinfunction "GND_2") (pintype "passive"))
      (node (ref "U11") (pin "2") (pinfunction "GND_2") (pintype "passive"))
      (node (ref "U12") (pin "2") (pinfunction "GND_2") (pintype "passive"))
      (node (ref "U13") (pin "2") (pinfunction "GND_2") (pintype "passive"))
      (node (ref "U14") (pin "2") (pinfunction "GND_2") (pintype "passive"))
      (node (ref "U15") (pin "2") (pinfunction "GND_2") (pintype "passive"))
      (node (ref "U16") (pin "2") (pinfunction "GND_2") (pintype "passive"))
      (node (ref "U17") (pin "2") (pinfunction "GND_2") (pintype "passive"))
      (node (ref "U2") (pin "18") (pinfunction "GND2_18") (pintype "power_in"))
      (node (ref "U2") (pin "5") (pinfunction "NC/GND_5") (pintype "bidirectional"))
      (node (ref "U2") (pin "PAD") (pinfunction "GND_PAD") (pintype "power_in"))
      (node (ref "U3") (pin "1") (pinfunction "GND1_1") (pintype "bidirectional"))
      (node (ref "U3") (pin "18") (pinfunction "GND3_18") (pintype "bidirectional"))
      (node (ref "U3") (pin "20") (pinfunction "GND4_20") (pintype "bidirectional"))
      (node (ref "U3") (pin "23") (pinfunction "GND5_23") (pintype "bidirectional"))
      (node (ref "U3") (pin "24") (pinfunction "GND6_24") (pintype "bidirectional"))
      (node (ref "U3") (pin "25") (pinfunction "GND7_25") (pintype "bidirectional"))
      (node (ref "U3") (pin "26") (pinfunction "GND8_26") (pintype "bidirectional"))
      (node (ref "U3") (pin "28") (pinfunction "GND9_28") (pintype "bidirectional"))
      (node (ref "U3") (pin "29") (pinfunction "GND10_29") (pintype "bidirectional"))
      (node (ref "U3") (pin "5") (pinfunction "GND2_5") (pintype "bidirectional"))
      (node (ref "U4") (pin "4") (pinfunction "VSS_4") (pintype "power_in"))
      (node (ref "U4") (pin "P$9") (pinfunction "GND_PAD_P$9") (pintype "power_in"))
      (node (ref "U5") (pin "2") (pinfunction "GND_2") (pintype "power_in"))
      (node (ref "U6") (pin "2") (pinfunction "GND_2") (pintype "power_in"))
      (node (ref "U7") (pin "2") (pinfunction "GND_2") (pintype "bidirectional"))
      (node (ref "U8") (pin "3") (pinfunction "GND_3") (pintype "passive"))
      (node (ref "U9") (pin "3") (pinfunction "GND_3") (pintype "bidirectional"))
      (node (ref "U9") (pin "4") (pinfunction "CSB1_4") (pintype "bidirectional"))
      (node (ref "U9") (pin "5") (pinfunction "CSB2_5") (pintype "bidirectional"))
    )
    (net (code "45") (name "Net-(C2-P$1)") (class "Default")
      (node (ref "C2") (pin "1") (pinfunction "P$1_1") (pintype "passive"))
      (node (ref "L4") (pin "1") (pinfunction "1_1") (pintype "passive"))
      (node (ref "L5") (pin "2") (pinfunction "2_2") (pintype "passive"))
    )
    (net (code "46") (name "Net-(C3-P$1)") (class "Default")
      (node (ref "C3") (pin "1") (pinfunction "P$1_1") (pintype "passive"))
      (node (ref "C6") (pin "1") (pinfunction "P$1_1") (pintype "passive"))
      (node (ref "L3") (pin "1") (pinfunction "1_1") (pintype "passive"))
      (node (ref "L4") (pin "2") (pinfunction "2_2") (pintype "passive"))
      (node (ref "L7") (pin "1") (pinfunction "1_1") (pintype "passive"))
    )
    (net (code "47") (name "Net-(C4-P$1)") (class "Default")
      (node (ref "C4") (pin "1") (pinfunction "P$1_1") (pintype "passive"))
      (node (ref "L3") (pin "2") (pinfunction "2_2") (pintype "passive"))
    )
    (net (code "48") (name "Net-(C4-P$2)") (class "Default")
      (node (ref "C4") (pin "2") (pinfunction "P$2_2") (pintype "passive"))
      (node (ref "L2") (pin "1") (pinfunction "1_1") (pintype "passive"))
      (node (ref "U2") (pin "4") (pinfunction "TX_4") (pintype "output"))
    )
    (net (code "49") (name "Net-(C5-P$1)") (class "Default")
      (node (ref "C5") (pin "1") (pinfunction "P$1_1") (pintype "passive"))
      (node (ref "L6") (pin "1") (pinfunction "1_1") (pintype "passive"))
      (node (ref "L7") (pin "2") (pinfunction "2_2") (pintype "passive"))
      (node (ref "U2") (pin "3") (pinfunction "RXN_3") (pintype "input"))
    )
    (net (code "50") (name "Net-(C6-P$2)") (class "Default")
      (node (ref "C6") (pin "2") (pinfunction "P$2_2") (pintype "passive"))
      (node (ref "L6") (pin "2") (pinfunction "2_2") (pintype "passive"))
      (node (ref "U2") (pin "2") (pinfunction "RXP_2") (pintype "input"))
    )
    (net (code "51") (name "Net-(C10-P$1)") (class "Default")
      (node (ref "C10") (pin "1") (pinfunction "P$1_1") (pintype "passive"))
      (node (ref "C21") (pin "1") (pinfunction "P$1_1") (pintype "passive"))
      (node (ref "C32") (pin "1") (pinfunction "P$1_1") (pintype "passive"))
      (node (ref "U10") (pin "5") (pinfunction "OUT_5") (pintype "output"))
      (node (ref "U4") (pin "7") (pinfunction "~{HOLD}_7") (pintype "output"))
      (node (ref "U4") (pin "8") (pinfunction "VDD_8") (pintype "power_in"))
    )
    (net (code "52") (name "Net-(C12-P$1)") (class "Default")
      (node (ref "C12") (pin "1") (pinfunction "P$1_1") (pintype "passive"))
      (node (ref "U11") (pin "4") (pinfunction "NR/FB_4") (pintype "passive"))
    )
    (net (code "53") (name "Net-(C15-P$1)") (class "Default")
      (node (ref "C15") (pin "1") (pinfunction "P$1_1") (pintype "passive"))
      (node (ref "C47") (pin "1") (pinfunction "P$1_1") (pintype "passive"))
      (node (ref "U1") (pin "30") (pinfunction "VDD_30") (pintype "power_in"))
      (node (ref "U16") (pin "5") (pinfunction "OUT_5") (pintype "output"))
    )
    (net (code "54") (name "Net-(C16-P$1)") (class "Default")
      (node (ref "C16") (pin "1") (pinfunction "P$1_1") (pintype "passive"))
      (node (ref "U1") (pin "29") (pinfunction "VDD_CORE_29") (pintype "power_in"))
    )
    (net (code "55") (name "Net-(C19-P$1)") (class "Default")
      (node (ref "C19") (pin "1") (pinfunction "P$1_1") (pintype "passive"))
      (node (ref "C26") (pin "1") (pinfunction "P$1_1") (pintype "passive"))
      (node (ref "C35") (pin "1") (pinfunction "P$1_1") (pintype "passive"))
      (node (ref "U12") (pin "5") (pinfunction "OUT_5") (pintype "output"))
      (node (ref "U9") (pin "1") (pinfunction "VDD_1") (pintype "bidirectional"))
      (node (ref "U9") (pin "2") (pinfunction "PS_2") (pintype "bidirectional"))
    )
    (net (code "56") (name "Net-(C20-P$1)") (class "Default")
      (node (ref "C20") (pin "1") (pinfunction "P$1_1") (pintype "passive"))
      (node (ref "C25") (pin "1") (pinfunction "P$1_1") (pintype "passive"))
      (node (ref "C41") (pin "1") (pinfunction "P$1_1") (pintype "passive"))
      (node (ref "C7") (pin "1") (pinfunction "P$1_1") (pintype "passive"))
      (node (ref "C8") (pin "1") (pinfunction "P$1_1") (pintype "passive"))
      (node (ref "L2") (pin "2") (pinfunction "2_2") (pintype "passive"))
      (node (ref "U14") (pin "5") (pinfunction "OUT_5") (pintype "output"))
    )
    (net (code "57") (name "Net-(C29-P$1)") (class "Default")
      (node (ref "C29") (pin "1") (pinfunction "P$1_1") (pintype "passive"))
      (node (ref "U10") (pin "4") (pinfunction "NR/FB_4") (pintype "passive"))
    )
    (net (code "58") (name "Net-(C30-P$1)") (class "Default")
      (node (ref "C30") (pin "1") (pinfunction "P$1_1") (pintype "passive"))
      (node (ref "JP3") (pin "1") (pinfunction "1_1") (pintype "passive"))
      (node (ref "U10") (pin "1") (pinfunction "IN_1") (pintype "power_in"))
      (node (ref "U10") (pin "3") (pinfunction "EN_3") (pintype "input"))
    )
    (net (code "59") (name "Net-(C33-P$1)") (class "Default")
      (node (ref "C33") (pin "1") (pinfunction "P$1_1") (pintype "passive"))
      (node (ref "U12") (pin "4") (pinfunction "NR/FB_4") (pintype "passive"))
    )
    (net (code "60") (name "Net-(C34-P$1)") (class "Default")
      (node (ref "C34") (pin "1") (pinfunction "P$1_1") (pintype "passive"))
      (node (ref "JP4") (pin "1") (pinfunction "1_1") (pintype "passive"))
      (node (ref "U12") (pin "1") (pinfunction "IN_1") (pintype "power_in"))
      (node (ref "U12") (pin "3") (pinfunction "EN_3") (pintype "input"))
    )
    (net (code "61") (name "Net-(C36-P$1)") (class "Default")
      (node (ref "C36") (pin "1") (pinfunction "P$1_1") (pintype "passive"))
      (node (ref "U13") (pin "4") (pinfunction "NR/FB_4") (pintype "passive"))
    )
    (net (code "62") (name "Net-(C37-P$1)") (class "Default")
      (node (ref "C37") (pin "1") (pinfunction "P$1_1") (pintype "passive"))
      (node (ref "JP5") (pin "1") (pinfunction "1_1") (pintype "passive"))
      (node (ref "U13") (pin "1") (pinfunction "IN_1") (pintype "power_in"))
      (node (ref "U13") (pin "3") (pinfunction "EN_3") (pintype "input"))
    )
    (net (code "63") (name "Net-(C39-P$1)") (class "Default")
      (node (ref "C39") (pin "1") (pinfunction "P$1_1") (pintype "passive"))
      (node (ref "U14") (pin "4") (pinfunction "NR/FB_4") (pintype "passive"))
    )
    (net (code "64") (name "Net-(C40-P$1)") (class "Default")
      (node (ref "C40") (pin "1") (pinfunction "P$1_1") (pintype "passive"))
      (node (ref "JP6") (pin "1") (pinfunction "1_1") (pintype "passive"))
      (node (ref "U14") (pin "1") (pinfunction "IN_1") (pintype "power_in"))
      (node (ref "U14") (pin "3") (pinfunction "EN_3") (pintype "input"))
    )
    (net (code "65") (name "Net-(C42-P$1)") (class "Default")
      (node (ref "C42") (pin "1") (pinfunction "P$1_1") (pintype "passive"))
      (node (ref "U15") (pin "4") (pinfunction "NR/FB_4") (pintype "passive"))
    )
    (net (code "66") (name "Net-(C43-P$1)") (class "Default")
      (node (ref "C43") (pin "1") (pinfunction "P$1_1") (pintype "passive"))
      (node (ref "JP7") (pin "2") (pinfunction "2_2") (pintype "passive"))
      (node (ref "U15") (pin "1") (pinfunction "IN_1") (pintype "power_in"))
      (node (ref "U15") (pin "3") (pinfunction "EN_3") (pintype "input"))
    )
    (net (code "67") (name "Net-(C44-P$1)") (class "Default")
      (node (ref "C44") (pin "1") (pinfunction "P$1_1") (pintype "passive"))
      (node (ref "U15") (pin "5") (pinfunction "OUT_5") (pintype "output"))
      (node (ref "U2") (pin "6") (pinfunction "VDD_6") (pintype "power_in"))
      (node (ref "U2") (pin "8") (pinfunction "VDD2_8") (pintype "power_in"))
    )
    (net (code "68") (name "Net-(C45-P$1)") (class "Default")
      (node (ref "C45") (pin "1") (pinfunction "P$1_1") (pintype "passive"))
      (node (ref "U16") (pin "4") (pinfunction "NR/FB_4") (pintype "passive"))
    )
    (net (code "69") (name "Net-(C46-P$1)") (class "Default")
      (node (ref "C46") (pin "1") (pinfunction "P$1_1") (pintype "passive"))
      (node (ref "JP9") (pin "1") (pinfunction "1_1") (pintype "passive"))
      (node (ref "U16") (pin "1") (pinfunction "IN_1") (pintype "power_in"))
      (node (ref "U16") (pin "3") (pinfunction "EN_3") (pintype "input"))
    )
    (net (code "70") (name "Net-(C48-P$1)") (class "Default")
      (node (ref "C48") (pin "1") (pinfunction "P$1_1") (pintype "passive"))
      (node (ref "U17") (pin "4") (pinfunction "NR/FB_4") (pintype "passive"))
    )
    (net (code "71") (name "Net-(C49-P$1)") (class "Default")
      (node (ref "C49") (pin "1") (pinfunction "P$1_1") (pintype "passive"))
      (node (ref "JP10") (pin "1") (pinfunction "1_1") (pintype "passive"))
      (node (ref "U17") (pin "1") (pinfunction "IN_1") (pintype "power_in"))
      (node (ref "U17") (pin "3") (pinfunction "EN_3") (pintype "input"))
    )
    (net (code "72") (name "Net-(C50-P$1)") (class "Default")
      (node (ref "C50") (pin "1") (pinfunction "P$1_1") (pintype "passive"))
      (node (ref "U1") (pin "9") (pinfunction "VDD_ANA_9") (pintype "power_in"))
      (node (ref "U17") (pin "5") (pinfunction "OUT_5") (pintype "output"))
    )
    (net (code "73") (name "Net-(JP1-Pad1)") (class "Default")
      (node (ref "JP1") (pin "1") (pinfunction "1_1") (pintype "passive"))
      (node (ref "JTAG1") (pin "1") (pinfunction "1_1") (pintype "passive"))
    )
    (net (code "74") (name "Net-(U3-CTS_SPI)") (class "Default")
      (node (ref "R4") (pin "1") (pinfunction "1_1") (pintype "passive"))
      (node (ref "U3") (pin "31") (pinfunction "CTS_SPI_31") (pintype "bidirectional"))
    )
    (net (code "75") (name "Net-(U3-GPIO0)") (class "Default")
      (node (ref "R2") (pin "2") (pinfunction "2_2") (pintype "passive"))
      (node (ref "U3") (pin "17") (pinfunction "GPIO0_17") (pintype "bidirectional"))
    )
    (net (code "76") (name "Net-(U3-GPIO1)") (class "Default")
      (node (ref "R3") (pin "2") (pinfunction "2_2") (pintype "passive"))
      (node (ref "U3") (pin "16") (pinfunction "GPIO1_16") (pintype "bidirectional"))
    )
    (net (code "77") (name "Net-(U3-VBB_I)") (class "Default")
      (node (ref "JP14") (pin "1") (pinfunction "1_1") (pintype "passive"))
      (node (ref "L8") (pin "1") (pinfunction "1_1") (pintype "passive"))
      (node (ref "U3") (pin "6") (pinfunction "VBB_I_6") (pintype "bidirectional"))
    )
    (net (code "78") (name "Net-(U3-VREG_O)") (class "Default")
      (node (ref "JP14") (pin "2") (pinfunction "2_2") (pintype "passive"))
      (node (ref "L8") (pin "2") (pinfunction "2_2") (pintype "passive"))
      (node (ref "U3") (pin "7") (pinfunction "VREG_O_7") (pintype "bidirectional"))
    )
    (net (code "79") (name "unconnected-(A1-N{slash}C-Pad2)") (class "Default")
      (node (ref "A1") (pin "2") (pinfunction "N/C_2") (pintype "input"))
    )
    (net (code "80") (name "unconnected-(JTAG1-Pad6)") (class "Default")
      (node (ref "JTAG1") (pin "6") (pinfunction "6_6") (pintype "passive"))
    )
    (net (code "81") (name "unconnected-(JTAG1-Pad7)") (class "Default")
      (node (ref "JTAG1") (pin "7") (pinfunction "7_7") (pintype "passive"))
    )
    (net (code "82") (name "unconnected-(JTAG1-Pad8)") (class "Default")
      (node (ref "JTAG1") (pin "8") (pinfunction "8_8") (pintype "passive"))
    )
    (net (code "83") (name "unconnected-(JTAG1-Pad9)") (class "Default")
      (node (ref "JTAG1") (pin "9") (pinfunction "9_9") (pintype "passive"))
    )
    (net (code "84") (name "unconnected-(U2-GPIO2-Pad19)") (class "Default")
      (node (ref "U2") (pin "19") (pinfunction "GPIO2_19") (pintype "bidirectional"))
    )
    (net (code "85") (name "unconnected-(U2-GPIO3-Pad20)") (class "Default")
      (node (ref "U2") (pin "20") (pinfunction "GPIO3_20") (pintype "bidirectional"))
    )
    (net (code "86") (name "unconnected-(U2-TXRAMP-Pad7)") (class "Default")
      (node (ref "U2") (pin "7") (pinfunction "TXRAMP_7") (pintype "bidirectional"))
    )
    (net (code "87") (name "unconnected-(U2-XOUT-Pad16)") (class "Default")
      (node (ref "U2") (pin "16") (pinfunction "XOUT_16") (pintype "output"))
    )
    (net (code "88") (name "unconnected-(U3-GPIO2-Pad15)") (class "Default")
      (node (ref "U3") (pin "15") (pinfunction "GPIO2_15") (pintype "bidirectional"))
    )
    (net (code "89") (name "unconnected-(U3-GPIO3-Pad11)") (class "Default")
      (node (ref "U3") (pin "11") (pinfunction "GPIO3_11") (pintype "bidirectional"))
    )
    (net (code "90") (name "unconnected-(U3-GPIO4-Pad14)") (class "Default")
      (node (ref "U3") (pin "14") (pinfunction "GPIO4_14") (pintype "bidirectional"))
    )
    (net (code "91") (name "unconnected-(U3-GPIO8-Pad10)") (class "Default")
      (node (ref "U3") (pin "10") (pinfunction "GPIO8_10") (pintype "bidirectional"))
    )
    (net (code "92") (name "unconnected-(U3-NSRESET-Pad30)") (class "Default")
      (node (ref "U3") (pin "30") (pinfunction "NSRESET_30") (pintype "bidirectional"))
    )
    (net (code "93") (name "unconnected-(U3-RTS_SPI-Pad32)") (class "Default")
      (node (ref "U3") (pin "32") (pinfunction "RTS_SPI_32") (pintype "bidirectional"))
    )
    (net (code "94") (name "unconnected-(U3-SYSTEM_ON-Pad2)") (class "Default")
      (node (ref "U3") (pin "2") (pinfunction "SYSTEM_ON_2") (pintype "bidirectional"))
    )
    (net (code "95") (name "unconnected-(U3-XTAL_CLK-Pad22)") (class "Default")
      (node (ref "U3") (pin "22") (pinfunction "XTAL_CLK_22") (pintype "bidirectional"))
    )
    (net (code "96") (name "unconnected-(U5-NC-Pad1)") (class "Default")
      (node (ref "U5") (pin "1") (pinfunction "NC_1") (pintype "no_connect"))
    )
    (net (code "97") (name "unconnected-(U6-NC-Pad1)") (class "Default")
      (node (ref "U6") (pin "1") (pinfunction "NC_1") (pintype "no_connect"))
    )
    (net (code "98") (name "unconnected-(U9-SDO-Pad6)") (class "Default")
      (node (ref "U9") (pin "6") (pinfunction "SDO_6") (pintype "bidirectional"))
    )
  )
)
